# smallscale.net
KiCad netlist of a schematic drawn in EAGLE
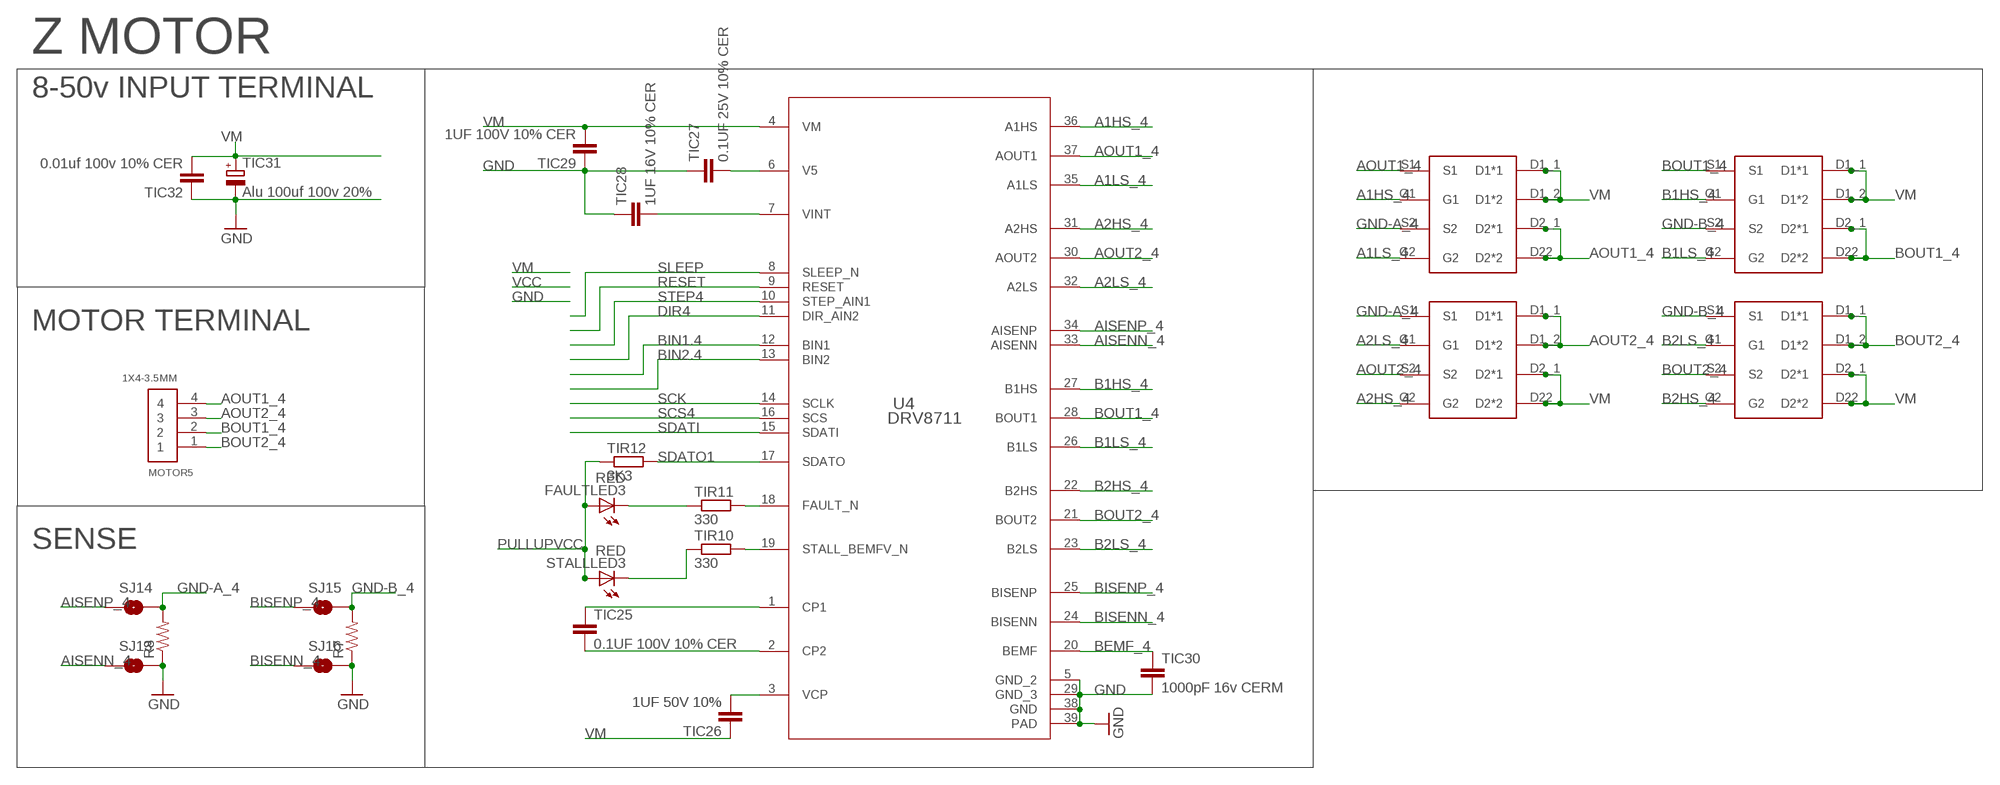
[diagram p0: schematic, sheet 1]
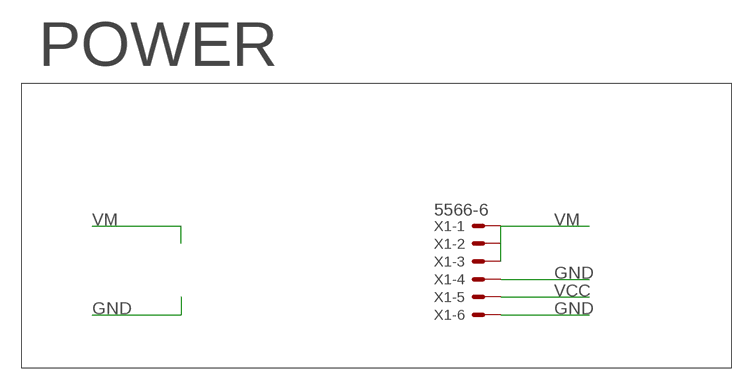
[diagram p1: schematic, sheet 2]

(export (version "E")
  (design (tool "Eeschema 10.0.6"))
  (components
    (comp (ref "X1")
      (value "5566-6")
      (footprint "eagle-import:5566-6")
      (fields (field (name "MPN") "95566-61002"))
      (libsource (lib "eagle-import") (part "5566-6"))
    )
    (comp (ref "FAULTLED3")
      (value "RED")
      (footprint "eagle-import:1206")
      (libsource (lib "eagle-import") (part "LEDSMT1206"))
    )
    (comp (ref "MOTOR5")
      (value "1X4-3.5MM")
      (footprint "eagle-import:1X04-3.5MM")
      (libsource (lib "eagle-import") (part "1X4-3.5MM"))
    )
    (comp (ref "R7")
      (value "R-US_R2512")
      (footprint "eagle-import:R2512")
      (libsource (lib "eagle-import") (part "R-US_R2512"))
    )
    (comp (ref "R8")
      (value "R-US_R2512")
      (footprint "eagle-import:R2512")
      (libsource (lib "eagle-import") (part "R-US_R2512"))
    )
    (comp (ref "SJ13")
      (value "SOLDERJUMPERTRACE")
      (footprint "eagle-import:SJ_2S-TRACE")
      (libsource (lib "eagle-import") (part "SOLDERJUMPERTRACE"))
    )
    (comp (ref "SJ14")
      (value "SOLDERJUMPERTRACE")
      (footprint "eagle-import:SJ_2S-TRACE")
      (libsource (lib "eagle-import") (part "SOLDERJUMPERTRACE"))
    )
    (comp (ref "SJ15")
      (value "SOLDERJUMPERTRACE")
      (footprint "eagle-import:SJ_2S-TRACE")
      (libsource (lib "eagle-import") (part "SOLDERJUMPERTRACE"))
    )
    (comp (ref "SJ16")
      (value "SOLDERJUMPERTRACE")
      (footprint "eagle-import:SJ_2S-TRACE")
      (libsource (lib "eagle-import") (part "SOLDERJUMPERTRACE"))
    )
    (comp (ref "STALLLED3")
      (value "RED")
      (footprint "eagle-import:1206")
      (libsource (lib "eagle-import") (part "LEDSMT1206"))
    )
    (comp (ref "TIC25")
      (value "0.1UF 100V 10% CER")
      (footprint "eagle-import:C0603K")
      (libsource (lib "eagle-import") (part "C-EUC0603K"))
    )
    (comp (ref "TIC26")
      (value "1UF 50V 10%")
      (footprint "eagle-import:C0805K")
      (libsource (lib "eagle-import") (part "C-EUC0805K"))
    )
    (comp (ref "TIC27")
      (value "0.1UF 25V 10% CER")
      (footprint "eagle-import:C0603K")
      (libsource (lib "eagle-import") (part "C-EUC0603K"))
    )
    (comp (ref "TIC28")
      (value "1UF 16V 10% CER")
      (footprint "eagle-import:C0603K")
      (libsource (lib "eagle-import") (part "C-EUC0603K"))
    )
    (comp (ref "TIC29")
      (value "1UF 100V 10% CER")
      (footprint "eagle-import:C1206K")
      (libsource (lib "eagle-import") (part "C-EUC1206K"))
    )
    (comp (ref "TIC30")
      (value "1000pF 16v CERM")
      (footprint "eagle-import:C0603K")
      (libsource (lib "eagle-import") (part "C-EUC0603K"))
    )
    (comp (ref "TIC31")
      (value "Alu 100uf 100v 20%")
      (footprint "eagle-import:E5-10,5")
      (libsource (lib "eagle-import") (part "CPOL-EUE5-10.5"))
    )
    (comp (ref "TIC32")
      (value "0.01uf 100v 10% CER")
      (footprint "eagle-import:C0603K")
      (libsource (lib "eagle-import") (part "C-EUC0603K"))
    )
    (comp (ref "TIR10")
      (value "330")
      (footprint "eagle-import:R1206")
      (libsource (lib "eagle-import") (part "R-EU_R1206"))
    )
    (comp (ref "TIR11")
      (value "330")
      (footprint "eagle-import:R1206")
      (libsource (lib "eagle-import") (part "R-EU_R1206"))
    )
    (comp (ref "TIR12")
      (value "3K3")
      (footprint "eagle-import:R1206")
      (libsource (lib "eagle-import") (part "R-EU_R1206"))
    )
    (comp (ref "U$13")
      (value "CSD88537ND")
      (footprint "eagle-import:CSD88537ND")
      (libsource (lib "eagle-import") (part "CSD88537ND"))
    )
    (comp (ref "U$14")
      (value "CSD88537ND")
      (footprint "eagle-import:CSD88537ND")
      (libsource (lib "eagle-import") (part "CSD88537ND"))
    )
    (comp (ref "U$15")
      (value "CSD88537ND")
      (footprint "eagle-import:CSD88537ND")
      (libsource (lib "eagle-import") (part "CSD88537ND"))
    )
    (comp (ref "U$16")
      (value "CSD88537ND")
      (footprint "eagle-import:CSD88537ND")
      (libsource (lib "eagle-import") (part "CSD88537ND"))
    )
    (comp (ref "U4")
      (value "DRV8711")
      (footprint "eagle-import:DCP0038A_N")
      (fields
        (field (name "ALTERNATEPARTNUMBER") "DRV8711DCP")
        (field (name "MANUFACTURER") "Texas Instruments")
        (field (name "PARTNUMBER") "DRV8711DCPR")
      )
      (libsource (lib "eagle-import") (part "DRV8711DCPR"))
    )
  )
  (nets
    (net (code "1") (name "A1HS_4") (class "Default")
      (node (ref "U$13") (pin "G1") (pinfunction "G1_G1") (pintype "power_in"))
      (node (ref "U4") (pin "36") (pinfunction "A1HS_36") (pintype "output"))
    )
    (net (code "2") (name "A1LS_4") (class "Default")
      (node (ref "U$13") (pin "G2") (pinfunction "G2_G2") (pintype "power_in"))
      (node (ref "U4") (pin "35") (pinfunction "A1LS_35") (pintype "output"))
    )
    (net (code "3") (name "A2HS_4") (class "Default")
      (node (ref "U$15") (pin "G2") (pinfunction "G2_G2") (pintype "power_in"))
      (node (ref "U4") (pin "31") (pinfunction "A2HS_31") (pintype "output"))
    )
    (net (code "4") (name "A2LS_4") (class "Default")
      (node (ref "U$15") (pin "G1") (pinfunction "G1_G1") (pintype "power_in"))
      (node (ref "U4") (pin "32") (pinfunction "A2LS_32") (pintype "output"))
    )
    (net (code "5") (name "AISENN_4") (class "Default")
      (node (ref "SJ13") (pin "1") (pinfunction "1_1") (pintype "passive"))
      (node (ref "U4") (pin "33") (pinfunction "AISENN_33") (pintype "input"))
    )
    (net (code "6") (name "AISENP_4") (class "Default")
      (node (ref "SJ14") (pin "1") (pinfunction "1_1") (pintype "passive"))
      (node (ref "U4") (pin "34") (pinfunction "AISENP_34") (pintype "input"))
    )
    (net (code "7") (name "AOUT1_4") (class "Default")
      (node (ref "MOTOR5") (pin "4") (pinfunction "4_4") (pintype "bidirectional"))
      (node (ref "U$13") (pin "D22") (pinfunction "D2*2_D22") (pintype "power_in"))
      (node (ref "U$13") (pin "D2_1") (pinfunction "D2*1_D2_1") (pintype "power_in"))
      (node (ref "U$13") (pin "S1") (pinfunction "S1_S1") (pintype "power_in"))
      (node (ref "U4") (pin "37") (pinfunction "AOUT1_37") (pintype "output"))
    )
    (net (code "8") (name "AOUT2_4") (class "Default")
      (node (ref "MOTOR5") (pin "3") (pinfunction "3_3") (pintype "bidirectional"))
      (node (ref "U$15") (pin "D1_1") (pinfunction "D1*1_D1_1") (pintype "power_in"))
      (node (ref "U$15") (pin "D1_2") (pinfunction "D1*2_D1_2") (pintype "power_in"))
      (node (ref "U$15") (pin "S2") (pinfunction "S2_S2") (pintype "power_in"))
      (node (ref "U4") (pin "30") (pinfunction "AOUT2_30") (pintype "output"))
    )
    (net (code "9") (name "B1HS_4") (class "Default")
      (node (ref "U$14") (pin "G1") (pinfunction "G1_G1") (pintype "power_in"))
      (node (ref "U4") (pin "27") (pinfunction "B1HS_27") (pintype "output"))
    )
    (net (code "10") (name "B1LS_4") (class "Default")
      (node (ref "U$14") (pin "G2") (pinfunction "G2_G2") (pintype "power_in"))
      (node (ref "U4") (pin "26") (pinfunction "B1LS_26") (pintype "output"))
    )
    (net (code "11") (name "B2HS_4") (class "Default")
      (node (ref "U$16") (pin "G2") (pinfunction "G2_G2") (pintype "power_in"))
      (node (ref "U4") (pin "22") (pinfunction "B2HS_22") (pintype "output"))
    )
    (net (code "12") (name "B2LS_4") (class "Default")
      (node (ref "U$16") (pin "G1") (pinfunction "G1_G1") (pintype "power_in"))
      (node (ref "U4") (pin "23") (pinfunction "B2LS_23") (pintype "output"))
    )
    (net (code "13") (name "BEMF_4") (class "Default")
      (node (ref "TIC30") (pin "1") (pinfunction "1_1") (pintype "passive"))
      (node (ref "U4") (pin "20") (pinfunction "BEMF_20") (pintype "output"))
    )
    (net (code "14") (name "BIN1.4") (class "Default")
      (node (ref "U4") (pin "12") (pinfunction "BIN1_12") (pintype "input"))
    )
    (net (code "15") (name "BIN2.4") (class "Default")
      (node (ref "U4") (pin "13") (pinfunction "BIN2_13") (pintype "input"))
    )
    (net (code "16") (name "BISENN_4") (class "Default")
      (node (ref "SJ16") (pin "1") (pinfunction "1_1") (pintype "passive"))
      (node (ref "U4") (pin "24") (pinfunction "BISENN_24") (pintype "input"))
    )
    (net (code "17") (name "BISENP_4") (class "Default")
      (node (ref "SJ15") (pin "1") (pinfunction "1_1") (pintype "passive"))
      (node (ref "U4") (pin "25") (pinfunction "BISENP_25") (pintype "input"))
    )
    (net (code "18") (name "BOUT1_4") (class "Default")
      (node (ref "MOTOR5") (pin "2") (pinfunction "2_2") (pintype "bidirectional"))
      (node (ref "U$14") (pin "D22") (pinfunction "D2*2_D22") (pintype "power_in"))
      (node (ref "U$14") (pin "D2_1") (pinfunction "D2*1_D2_1") (pintype "power_in"))
      (node (ref "U$14") (pin "S1") (pinfunction "S1_S1") (pintype "power_in"))
      (node (ref "U4") (pin "28") (pinfunction "BOUT1_28") (pintype "output"))
    )
    (net (code "19") (name "BOUT2_4") (class "Default")
      (node (ref "MOTOR5") (pin "1") (pinfunction "1_1") (pintype "bidirectional"))
      (node (ref "U$16") (pin "D1_1") (pinfunction "D1*1_D1_1") (pintype "power_in"))
      (node (ref "U$16") (pin "D1_2") (pinfunction "D1*2_D1_2") (pintype "power_in"))
      (node (ref "U$16") (pin "S2") (pinfunction "S2_S2") (pintype "power_in"))
      (node (ref "U4") (pin "21") (pinfunction "BOUT2_21") (pintype "output"))
    )
    (net (code "20") (name "DIR4") (class "Default")
      (node (ref "U4") (pin "11") (pinfunction "DIR_AIN2_11") (pintype "input"))
    )
    (net (code "21") (name "GND") (class "Default")
      (node (ref "R7") (pin "1") (pinfunction "1_1") (pintype "passive"))
      (node (ref "R8") (pin "1") (pinfunction "1_1") (pintype "passive"))
      (node (ref "SJ13") (pin "2") (pinfunction "2_2") (pintype "passive"))
      (node (ref "SJ16") (pin "2") (pinfunction "2_2") (pintype "passive"))
      (node (ref "TIC27") (pin "1") (pinfunction "1_1") (pintype "passive"))
      (node (ref "TIC28") (pin "1") (pinfunction "1_1") (pintype "passive"))
      (node (ref "TIC29") (pin "1") (pinfunction "1_1") (pintype "passive"))
      (node (ref "TIC30") (pin "2") (pinfunction "2_2") (pintype "passive"))
      (node (ref "TIC31") (pin "-") (pinfunction "-_-") (pintype "passive"))
      (node (ref "TIC32") (pin "1") (pinfunction "1_1") (pintype "passive"))
      (node (ref "U4") (pin "29") (pinfunction "GND_3_29") (pintype "power_in"))
      (node (ref "U4") (pin "38") (pinfunction "GND_38") (pintype "power_in"))
      (node (ref "U4") (pin "39") (pinfunction "PAD_39") (pintype "power_in"))
      (node (ref "U4") (pin "5") (pinfunction "GND_2_5") (pintype "power_in"))
      (node (ref "X1") (pin "4") (pinfunction "S_4") (pintype "passive"))
      (node (ref "X1") (pin "6") (pinfunction "S_6") (pintype "passive"))
    )
    (net (code "22") (name "GND-A_4") (class "Default")
      (node (ref "R8") (pin "2") (pinfunction "2_2") (pintype "passive"))
      (node (ref "SJ14") (pin "2") (pinfunction "2_2") (pintype "passive"))
      (node (ref "U$13") (pin "S2") (pinfunction "S2_S2") (pintype "power_in"))
      (node (ref "U$15") (pin "S1") (pinfunction "S1_S1") (pintype "power_in"))
    )
    (net (code "23") (name "GND-B_4") (class "Default")
      (node (ref "R7") (pin "2") (pinfunction "2_2") (pintype "passive"))
      (node (ref "SJ15") (pin "2") (pinfunction "2_2") (pintype "passive"))
      (node (ref "U$14") (pin "S2") (pinfunction "S2_S2") (pintype "power_in"))
      (node (ref "U$16") (pin "S1") (pinfunction "S1_S1") (pintype "power_in"))
    )
    (net (code "24") (name "Net-(FAULTLED3-PadC)") (class "Default")
      (node (ref "FAULTLED3") (pin "C") (pinfunction "C_C") (pintype "passive"))
      (node (ref "TIR11") (pin "1") (pinfunction "1_1") (pintype "passive"))
    )
    (net (code "25") (name "Net-(STALLLED3-PadC)") (class "Default")
      (node (ref "STALLLED3") (pin "C") (pinfunction "C_C") (pintype "passive"))
      (node (ref "TIR10") (pin "1") (pinfunction "1_1") (pintype "passive"))
    )
    (net (code "26") (name "Net-(U4-CP1)") (class "Default")
      (node (ref "TIC25") (pin "1") (pinfunction "1_1") (pintype "passive"))
      (node (ref "U4") (pin "1") (pinfunction "CP1_1") (pintype "passive"))
    )
    (net (code "27") (name "Net-(U4-CP2)") (class "Default")
      (node (ref "TIC25") (pin "2") (pinfunction "2_2") (pintype "passive"))
      (node (ref "U4") (pin "2") (pinfunction "CP2_2") (pintype "passive"))
    )
    (net (code "28") (name "Net-(U4-FAULT_N)") (class "Default")
      (node (ref "TIR11") (pin "2") (pinfunction "2_2") (pintype "passive"))
      (node (ref "U4") (pin "18") (pinfunction "FAULT_N_18") (pintype "open_collector"))
    )
    (net (code "29") (name "Net-(U4-STALL_BEMFV_N)") (class "Default")
      (node (ref "TIR10") (pin "2") (pinfunction "2_2") (pintype "passive"))
      (node (ref "U4") (pin "19") (pinfunction "STALL_BEMFV_N_19") (pintype "open_collector"))
    )
    (net (code "30") (name "Net-(U4-V5)") (class "Default")
      (node (ref "TIC27") (pin "2") (pinfunction "2_2") (pintype "passive"))
      (node (ref "U4") (pin "6") (pinfunction "V5_6") (pintype "power_in"))
    )
    (net (code "31") (name "Net-(U4-VCP)") (class "Default")
      (node (ref "TIC26") (pin "2") (pinfunction "2_2") (pintype "passive"))
      (node (ref "U4") (pin "3") (pinfunction "VCP_3") (pintype "passive"))
    )
    (net (code "32") (name "Net-(U4-VINT)") (class "Default")
      (node (ref "TIC28") (pin "2") (pinfunction "2_2") (pintype "passive"))
      (node (ref "U4") (pin "7") (pinfunction "VINT_7") (pintype "power_in"))
    )
    (net (code "33") (name "PULLUPVCC") (class "Default")
      (node (ref "FAULTLED3") (pin "A") (pinfunction "A_A") (pintype "passive"))
      (node (ref "STALLLED3") (pin "A") (pinfunction "A_A") (pintype "passive"))
      (node (ref "TIR12") (pin "1") (pinfunction "1_1") (pintype "passive"))
    )
    (net (code "34") (name "RESET") (class "Default")
      (node (ref "U4") (pin "9") (pinfunction "RESET_9") (pintype "input"))
    )
    (net (code "35") (name "SCK") (class "Default")
      (node (ref "U4") (pin "14") (pinfunction "SCLK_14") (pintype "input"))
    )
    (net (code "36") (name "SCS4") (class "Default")
      (node (ref "U4") (pin "16") (pinfunction "SCS_16") (pintype "input"))
    )
    (net (code "37") (name "SDATI") (class "Default")
      (node (ref "U4") (pin "15") (pinfunction "SDATI_15") (pintype "input"))
    )
    (net (code "38") (name "SDATO1") (class "Default")
      (node (ref "TIR12") (pin "2") (pinfunction "2_2") (pintype "passive"))
      (node (ref "U4") (pin "17") (pinfunction "SDATO_17") (pintype "open_collector"))
    )
    (net (code "39") (name "SLEEP") (class "Default")
      (node (ref "U4") (pin "8") (pinfunction "SLEEP_N_8") (pintype "input"))
    )
    (net (code "40") (name "STEP4") (class "Default")
      (node (ref "U4") (pin "10") (pinfunction "STEP_AIN1_10") (pintype "input"))
    )
    (net (code "41") (name "VCC") (class "Default")
      (node (ref "X1") (pin "5") (pinfunction "S_5") (pintype "passive"))
    )
    (net (code "42") (name "VM") (class "Default")
      (node (ref "TIC26") (pin "1") (pinfunction "1_1") (pintype "passive"))
      (node (ref "TIC29") (pin "2") (pinfunction "2_2") (pintype "passive"))
      (node (ref "TIC31") (pin "+") (pinfunction "+_+") (pintype "passive"))
      (node (ref "TIC32") (pin "2") (pinfunction "2_2") (pintype "passive"))
      (node (ref "U$13") (pin "D1_1") (pinfunction "D1*1_D1_1") (pintype "power_in"))
      (node (ref "U$13") (pin "D1_2") (pinfunction "D1*2_D1_2") (pintype "power_in"))
      (node (ref "U$14") (pin "D1_1") (pinfunction "D1*1_D1_1") (pintype "power_in"))
      (node (ref "U$14") (pin "D1_2") (pinfunction "D1*2_D1_2") (pintype "power_in"))
      (node (ref "U$15") (pin "D22") (pinfunction "D2*2_D22") (pintype "power_in"))
      (node (ref "U$15") (pin "D2_1") (pinfunction "D2*1_D2_1") (pintype "power_in"))
      (node (ref "U$16") (pin "D22") (pinfunction "D2*2_D22") (pintype "power_in"))
      (node (ref "U$16") (pin "D2_1") (pinfunction "D2*1_D2_1") (pintype "power_in"))
      (node (ref "U4") (pin "4") (pinfunction "VM_4") (pintype "power_in"))
      (node (ref "X1") (pin "1") (pinfunction "S_1") (pintype "passive"))
      (node (ref "X1") (pin "2") (pinfunction "S_2") (pintype "passive"))
      (node (ref "X1") (pin "3") (pinfunction "S_3") (pintype "passive"))
    )
  )
)
